# Pinout.net
KiCad netlist of a schematic drawn in Altium Designer
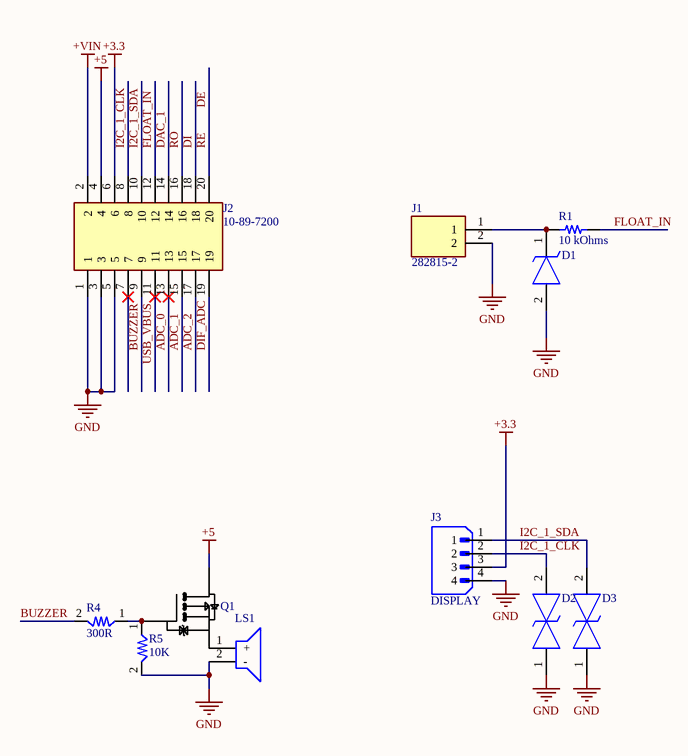
[diagram p0: Pinout.SchDoc]

(export (version "E")
  (design (tool "Eeschema 10.0.6"))
  (components
    (comp (ref "D1")
      (value "SMBJ5.0A")
      (footprint "SamacSys:SMBJ12A")
      (description "TVS Diode (Uni-directional)")
      (libsource (lib "*") (part "SMBJ5.0A"))
    )
    (comp (ref "D2")
      (value "DESD3V3Z1BCSF-7")
      (footprint "SamacSys:DESD3V3Z1BCSF7")
      (description "TVS Diode (Bi-directional)")
      (fields (field (name "MOUSER PART NUMBER") "621-DESD3V3Z1BCSF-7"))
      (libsource (lib "*") (part "DESD3V3Z1BCSF-7"))
    )
    (comp (ref "D3")
      (value "DESD3V3Z1BCSF-7")
      (footprint "SamacSys:DESD3V3Z1BCSF7")
      (description "TVS Diode (Bi-directional)")
      (fields (field (name "MOUSER PART NUMBER") "621-DESD3V3Z1BCSF-7"))
      (libsource (lib "*") (part "DESD3V3Z1BCSF-7"))
    )
    (comp (ref "J1")
      (value "282815-2")
      (footprint "SamacSys:SHDRRA2W102P0X508_1X2_1016X1200X850P")
      (description "Connector")
      (fields (field (name "MOUSER PART NUMBER") "571-282815-2"))
      (libsource (lib "*") (part "282815-2"))
    )
    (comp (ref "J2")
      (value "10-89-7200")
      (footprint "SamacSys:HDRV20W87P254_2X10_2553X508X864P")
      (description "Connector")
      (fields (field (name "MOUSER PART NUMBER") "538-10-89-7200"))
      (libsource (lib "*") (part "10-89-7200"))
    )
    (comp (ref "J3")
      (value "DISPLAY")
      (footprint "JST_B4B-XH-A(LF)(SN)")
      (description "Connector Header Through Hole 4 position 0.098 (2.50mm)")
      (fields (field (name "MF") "JST Sales") (field (name "MP") "B4B-XH-A(LF)(SN)"))
      (libsource (lib "Valve_Controller_Lib") (part "B4B-XH-A(LF)(SN)"))
    )
    (comp (ref "LS1")
      (value "CMI-1295IC-0585T")
      (footprint "CMI1295IC0585T")
      (description "Loudspeaker or Buzzer")
      (fields (field (name "MOUSER PART NUMBER") "490-CMI-1295IC-0585T"))
      (libsource (lib "Valve_Controller_Lib") (part "CMI-1295IC-0585T"))
    )
    (comp (ref "Q1")
      (value "DMG3415U-7")
      (footprint "SOT96P240X110-3N")
      (description "Integrated Circuit")
      (libsource (lib "Valve_Controller_Lib") (part "DMG3415U-7"))
    )
    (comp (ref "R1")
      (value "10 kOhms")
      (footprint "RES 0603_1608")
      (description "RES SMD 10K OHM 1% 1/10W 0603")
      (fields (field (name "PART NUMBER") "RT0603FRE0710KL") (field (name "MANUFACTURER") "Yageo"))
      (libsource (lib "dc_ups") (part "RT0603FRE0710KL"))
    )
    (comp (ref "R4")
      (value "300R")
      (footprint "RES0603")
      (description "Resistor")
      (fields (field (name "MANUFACTURER_PART_NUMBER") "0603WAF1001T5E"))
      (libsource (lib "Valve_Controller_Lib") (part "RES"))
    )
    (comp (ref "R5")
      (value "10K")
      (footprint "RES0603")
      (description "Resistor")
      (fields (field (name "MANUFACTURER_PART_NUMBER") "0603WAF1001T5E"))
      (libsource (lib "Valve_Controller_Lib") (part "RES"))
    )
  )
  (nets
    (net (code "1") (name "+3.3") (class "Default")
      (node (ref "J2") (pin "6") (pinfunction "6_6") (pintype "passive"))
      (node (ref "J3") (pin "3") (pinfunction "3_3") (pintype "passive"))
    )
    (net (code "2") (name "+5") (class "Default")
      (node (ref "J2") (pin "4") (pinfunction "4_4") (pintype "passive"))
      (node (ref "Q1") (pin "3") (pinfunction "D_3") (pintype "passive"))
    )
    (net (code "3") (name "+VIN") (class "Default")
      (node (ref "J2") (pin "2") (pinfunction "2_2") (pintype "passive"))
    )
    (net (code "4") (name "/ADC_0") (class "Default")
      (node (ref "J2") (pin "13") (pinfunction "13_13") (pintype "passive+no_connect"))
    )
    (net (code "5") (name "/ADC_1") (class "Default")
      (node (ref "J2") (pin "15") (pinfunction "15_15") (pintype "passive"))
    )
    (net (code "6") (name "/ADC_2") (class "Default")
      (node (ref "J2") (pin "17") (pinfunction "17_17") (pintype "passive"))
    )
    (net (code "7") (name "/BUZZER") (class "Default")
      (node (ref "J2") (pin "9") (pinfunction "9_9") (pintype "passive"))
      (node (ref "R4") (pin "2") (pinfunction "2_2") (pintype "passive"))
    )
    (net (code "8") (name "/DAC_1") (class "Default")
      (node (ref "J2") (pin "14") (pinfunction "14_14") (pintype "passive"))
    )
    (net (code "9") (name "/DE") (class "Default")
      (node (ref "J2") (pin "20") (pinfunction "20_20") (pintype "passive"))
    )
    (net (code "10") (name "/DI") (class "Default")
      (node (ref "J2") (pin "18") (pinfunction "18_18") (pintype "passive"))
    )
    (net (code "11") (name "/DIF_ADC") (class "Default")
      (node (ref "J2") (pin "19") (pinfunction "19_19") (pintype "passive"))
    )
    (net (code "12") (name "/FLOAT_IN") (class "Default")
      (node (ref "J2") (pin "12") (pinfunction "12_12") (pintype "passive"))
      (node (ref "R1") (pin "1") (pinfunction "1_1") (pintype "passive"))
    )
    (net (code "13") (name "/I2C_1_CLK") (class "Default")
      (node (ref "D2") (pin "2") (pinfunction "2_2") (pintype "passive"))
      (node (ref "J2") (pin "8") (pinfunction "8_8") (pintype "passive"))
      (node (ref "J3") (pin "2") (pinfunction "2_2") (pintype "passive"))
    )
    (net (code "14") (name "/I2C_1_SDA") (class "Default")
      (node (ref "D3") (pin "2") (pinfunction "2_2") (pintype "passive"))
      (node (ref "J2") (pin "10") (pinfunction "10_10") (pintype "passive"))
      (node (ref "J3") (pin "1") (pinfunction "1_1") (pintype "passive"))
    )
    (net (code "15") (name "/RO") (class "Default")
      (node (ref "J2") (pin "16") (pinfunction "16_16") (pintype "passive"))
    )
    (net (code "16") (name "/USB_VBUS") (class "Default")
      (node (ref "J2") (pin "11") (pinfunction "11_11") (pintype "passive+no_connect"))
    )
    (net (code "17") (name "GND") (class "Default")
      (node (ref "D1") (pin "2") (pinfunction "A_2") (pintype "passive"))
      (node (ref "D2") (pin "1") (pinfunction "1_1") (pintype "passive"))
      (node (ref "D3") (pin "1") (pinfunction "1_1") (pintype "passive"))
      (node (ref "J1") (pin "2") (pinfunction "2_2") (pintype "passive"))
      (node (ref "J2") (pin "1") (pinfunction "1_1") (pintype "passive"))
      (node (ref "J2") (pin "3") (pinfunction "3_3") (pintype "passive"))
      (node (ref "J2") (pin "5") (pinfunction "5_5") (pintype "passive"))
      (node (ref "J3") (pin "4") (pinfunction "4_4") (pintype "passive"))
      (node (ref "LS1") (pin "2") (pinfunction "-_2") (pintype "passive"))
      (node (ref "R5") (pin "2") (pinfunction "2_2") (pintype "passive"))
    )
    (net (code "18") (name "Net-(D1-K)") (class "Default")
      (node (ref "D1") (pin "1") (pinfunction "K_1") (pintype "passive"))
      (node (ref "J1") (pin "1") (pinfunction "1_1") (pintype "passive"))
      (node (ref "R1") (pin "2") (pinfunction "2_2") (pintype "passive"))
    )
    (net (code "19") (name "Net-(LS1-+)") (class "Default")
      (node (ref "LS1") (pin "1") (pinfunction "+_1") (pintype "passive"))
      (node (ref "Q1") (pin "2") (pinfunction "S_2") (pintype "passive"))
    )
    (net (code "20") (name "Net-(Q1-G)") (class "Default")
      (node (ref "Q1") (pin "1") (pinfunction "G_1") (pintype "passive"))
      (node (ref "R4") (pin "1") (pinfunction "1_1") (pintype "passive"))
      (node (ref "R5") (pin "1") (pinfunction "1_1") (pintype "passive"))
    )
    (net (code "21") (name "unconnected-(J2-Pad7)") (class "Default")
      (node (ref "J2") (pin "7") (pinfunction "7_7") (pintype "passive+no_connect"))
    )
  )
)
